# OUT.net
KiCad netlist of a schematic drawn in Altium Designer
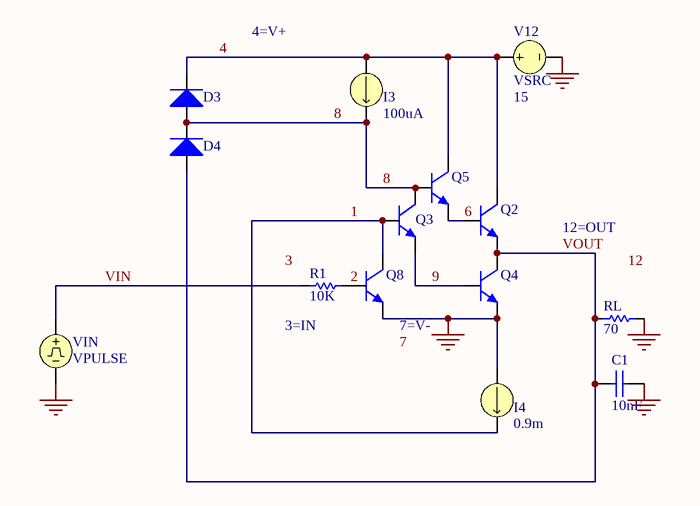
[diagram p0: OUT.SCHDOC]

(export (version "E")
  (design (tool "Eeschema 10.0.6"))
  (components
    (comp (ref "C1")
      (value "10nF")
      (footprint "0805")
      (description "Capacitor")
      (fields (field (name "VOLTAGE") "50V") (field (name "Comment") "Cap"))
      (libsource (lib "FEDE") (part "Cap"))
    )
    (comp (ref "D3")
      (value "Diode")
      (footprint "diode400")
      (description "Diodo")
      (libsource (lib "FEDE") (part "Diode"))
    )
    (comp (ref "D4")
      (value "Diode")
      (footprint "diode400")
      (description "Diodo")
      (libsource (lib "FEDE") (part "Diode"))
    )
    (comp (ref "I3")
      (value "100uA")
      (description "Current Source")
      (fields (field (name "Comment") "ISRC") (field (name "PUBLISHER") "Altium Limited"))
      (libsource (lib "Simulation Sources") (part "ISRC"))
    )
    (comp (ref "I4")
      (value "0.9m")
      (description "Current Source")
      (fields (field (name "Comment") "ISRC") (field (name "PUBLISHER") "Altium Limited"))
      (libsource (lib "Simulation Sources") (part "ISRC"))
    )
    (comp (ref "Q2")
      (value "NPN")
      (footprint "SOT23")
      (description "NPN Bipolar Transistor")
      (libsource (lib "FEDE") (part "NPN"))
    )
    (comp (ref "Q3")
      (value "NPN")
      (footprint "SOT23")
      (description "NPN Bipolar Transistor")
      (libsource (lib "FEDE") (part "NPN"))
    )
    (comp (ref "Q4")
      (value "NPN")
      (footprint "SOT23")
      (description "NPN Bipolar Transistor")
      (libsource (lib "FEDE") (part "NPN"))
    )
    (comp (ref "Q5")
      (value "NPN")
      (footprint "SOT23")
      (description "NPN Bipolar Transistor")
      (libsource (lib "FEDE") (part "NPN"))
    )
    (comp (ref "Q8")
      (value "NPN")
      (footprint "SOT23")
      (description "NPN Bipolar Transistor")
      (libsource (lib "FEDE") (part "NPN"))
    )
    (comp (ref "R1")
      (value "10K")
      (footprint "0805")
      (description "Resistor")
      (fields (field (name "POWER") "0.25W") (field (name "Comment") "Res"))
      (libsource (lib "FEDE") (part "Res"))
    )
    (comp (ref "RL")
      (value "70")
      (footprint "0805")
      (description "Resistor")
      (fields (field (name "POWER") "0.25W") (field (name "Comment") "Res"))
      (libsource (lib "FEDE") (part "Res"))
    )
    (comp (ref "V12")
      (value "VSRC")
      (description "Voltage Source")
      (fields (field (name "ALTIUM_VALUE") "15") (field (name "PUBLISHER") "Altium Limited"))
      (libsource (lib "Simulation Sources") (part "VSRC"))
    )
    (comp (ref "VIN")
      (value "VPULSE")
      (description "Pulse Voltage Source")
      (fields (field (name "PUBLISHER") "Altium Limited"))
      (libsource (lib "Simulation Sources") (part "VPULSE"))
    )
  )
  (nets
    (net (code "1") (name "/1") (class "Default")
      (node (ref "I4") (pin "2") (pinfunction "2_2") (pintype "passive"))
      (node (ref "Q3") (pin "2") (pinfunction "B_2") (pintype "passive"))
      (node (ref "Q8") (pin "1") (pinfunction "C_1") (pintype "passive"))
    )
    (net (code "2") (name "/2") (class "Default")
      (node (ref "Q8") (pin "2") (pinfunction "B_2") (pintype "passive"))
      (node (ref "R1") (pin "1") (pinfunction "1_1") (pintype "passive"))
    )
    (net (code "4") (name "/4") (class "Default")
      (node (ref "D3") (pin "2") (pinfunction "2_2") (pintype "passive"))
      (node (ref "I3") (pin "1") (pinfunction "1_1") (pintype "passive"))
      (node (ref "Q2") (pin "1") (pinfunction "C_1") (pintype "passive"))
      (node (ref "Q5") (pin "1") (pinfunction "C_1") (pintype "passive"))
      (node (ref "V12") (pin "1") (pinfunction "1_1") (pintype "passive"))
    )
    (net (code "5") (name "/6") (class "Default")
      (node (ref "Q2") (pin "2") (pinfunction "B_2") (pintype "passive"))
      (node (ref "Q5") (pin "3") (pinfunction "E_3") (pintype "passive"))
    )
    (net (code "7") (name "/8") (class "Default")
      (node (ref "D3") (pin "1") (pinfunction "1_1") (pintype "passive"))
      (node (ref "D4") (pin "2") (pinfunction "2_2") (pintype "passive"))
      (node (ref "I3") (pin "2") (pinfunction "2_2") (pintype "passive"))
      (node (ref "Q3") (pin "1") (pinfunction "C_1") (pintype "passive"))
      (node (ref "Q5") (pin "2") (pinfunction "B_2") (pintype "passive"))
    )
    (net (code "8") (name "/9") (class "Default")
      (node (ref "Q3") (pin "3") (pinfunction "E_3") (pintype "passive"))
      (node (ref "Q4") (pin "2") (pinfunction "B_2") (pintype "passive"))
    )
    (net (code "10") (name "/VIN") (class "Default")
      (node (ref "R1") (pin "2") (pinfunction "2_2") (pintype "passive"))
      (node (ref "VIN") (pin "1") (pinfunction "1_1") (pintype "passive"))
    )
    (net (code "11") (name "/VOUT") (class "Default")
      (node (ref "C1") (pin "2") (pinfunction "2_2") (pintype "passive"))
      (node (ref "D4") (pin "1") (pinfunction "1_1") (pintype "passive"))
      (node (ref "Q2") (pin "3") (pinfunction "E_3") (pintype "passive"))
      (node (ref "Q4") (pin "1") (pinfunction "C_1") (pintype "passive"))
      (node (ref "RL") (pin "1") (pinfunction "1_1") (pintype "passive"))
    )
    (net (code "12") (name "GND") (class "Default")
      (node (ref "C1") (pin "1") (pinfunction "1_1") (pintype "passive"))
      (node (ref "I4") (pin "1") (pinfunction "1_1") (pintype "passive"))
      (node (ref "Q4") (pin "3") (pinfunction "E_3") (pintype "passive"))
      (node (ref "Q8") (pin "3") (pinfunction "E_3") (pintype "passive"))
      (node (ref "RL") (pin "2") (pinfunction "2_2") (pintype "passive"))
      (node (ref "V12") (pin "2") (pinfunction "2_2") (pintype "passive"))
      (node (ref "VIN") (pin "2") (pinfunction "2_2") (pintype "passive"))
    )
  )
)
